# Booster_Capacitor.net
KiCad netlist of a schematic drawn in EAGLE
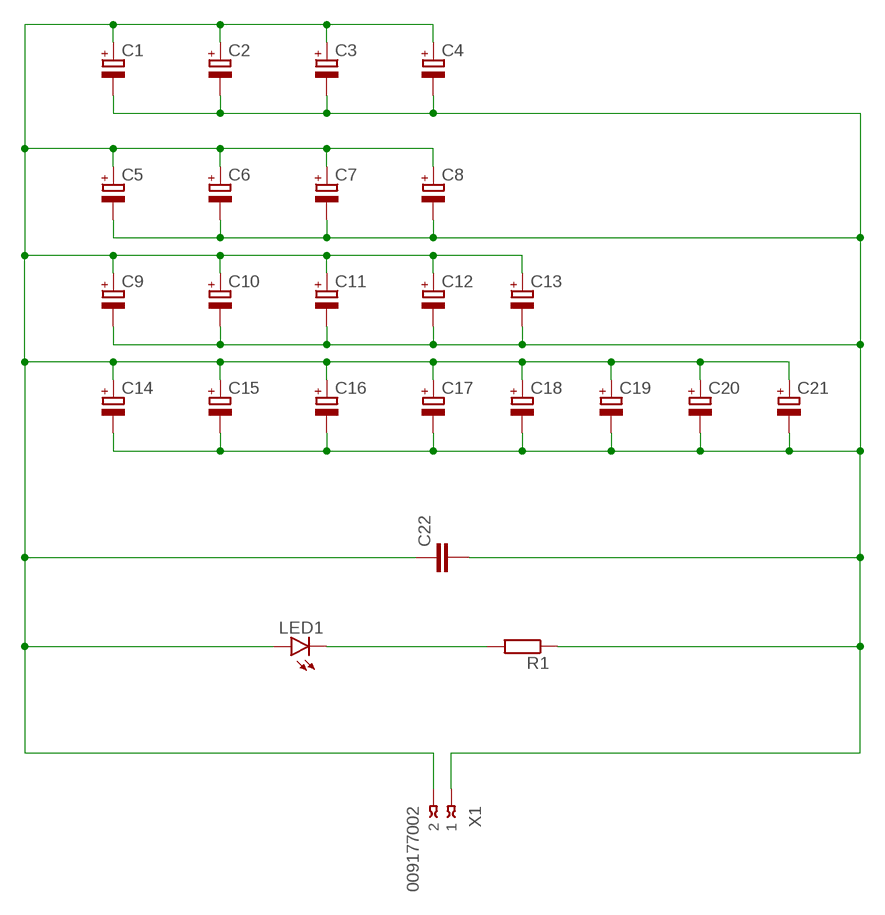
[diagram p0: schematic, sheet 1]

(export (version "E")
  (design (tool "Eeschema 10.0.6"))
  (components
    (comp (ref "C1")
      (value "CPOL-EUE3.5-8")
      (footprint "eagle-import:E3,5-8")
      (libsource (lib "eagle-import") (part "CPOL-EUE3.5-8"))
    )
    (comp (ref "C2")
      (value "CPOL-EUE3.5-8")
      (footprint "eagle-import:E3,5-8")
      (libsource (lib "eagle-import") (part "CPOL-EUE3.5-8"))
    )
    (comp (ref "C3")
      (value "CPOL-EUE3.5-8")
      (footprint "eagle-import:E3,5-8")
      (libsource (lib "eagle-import") (part "CPOL-EUE3.5-8"))
    )
    (comp (ref "C4")
      (value "CPOL-EUE3.5-8")
      (footprint "eagle-import:E3,5-8")
      (libsource (lib "eagle-import") (part "CPOL-EUE3.5-8"))
    )
    (comp (ref "C5")
      (value "CPOL-EUE3.5-8")
      (footprint "eagle-import:E3,5-8")
      (libsource (lib "eagle-import") (part "CPOL-EUE3.5-8"))
    )
    (comp (ref "C6")
      (value "CPOL-EUE3.5-8")
      (footprint "eagle-import:E3,5-8")
      (libsource (lib "eagle-import") (part "CPOL-EUE3.5-8"))
    )
    (comp (ref "C7")
      (value "CPOL-EUE3.5-8")
      (footprint "eagle-import:E3,5-8")
      (libsource (lib "eagle-import") (part "CPOL-EUE3.5-8"))
    )
    (comp (ref "C8")
      (value "CPOL-EUE3.5-8")
      (footprint "eagle-import:E3,5-8")
      (libsource (lib "eagle-import") (part "CPOL-EUE3.5-8"))
    )
    (comp (ref "C9")
      (value "CPOL-EUE2.5-7")
      (footprint "eagle-import:E2,5-7")
      (libsource (lib "eagle-import") (part "CPOL-EUE2.5-7"))
    )
    (comp (ref "C10")
      (value "CPOL-EUE2.5-7")
      (footprint "eagle-import:E2,5-7")
      (libsource (lib "eagle-import") (part "CPOL-EUE2.5-7"))
    )
    (comp (ref "C11")
      (value "CPOL-EUE2.5-7")
      (footprint "eagle-import:E2,5-7")
      (libsource (lib "eagle-import") (part "CPOL-EUE2.5-7"))
    )
    (comp (ref "C12")
      (value "CPOL-EUE2.5-7")
      (footprint "eagle-import:E2,5-7")
      (libsource (lib "eagle-import") (part "CPOL-EUE2.5-7"))
    )
    (comp (ref "C13")
      (value "CPOL-EUE2.5-7")
      (footprint "eagle-import:E2,5-7")
      (libsource (lib "eagle-import") (part "CPOL-EUE2.5-7"))
    )
    (comp (ref "C14")
      (value "CPOL-EUE2.5-6")
      (footprint "eagle-import:E2,5-6")
      (libsource (lib "eagle-import") (part "CPOL-EUE2.5-6"))
    )
    (comp (ref "C15")
      (value "CPOL-EUE2.5-6")
      (footprint "eagle-import:E2,5-6")
      (libsource (lib "eagle-import") (part "CPOL-EUE2.5-6"))
    )
    (comp (ref "C16")
      (value "CPOL-EUE2.5-6")
      (footprint "eagle-import:E2,5-6")
      (libsource (lib "eagle-import") (part "CPOL-EUE2.5-6"))
    )
    (comp (ref "C17")
      (value "CPOL-EUE2.5-6")
      (footprint "eagle-import:E2,5-6")
      (libsource (lib "eagle-import") (part "CPOL-EUE2.5-6"))
    )
    (comp (ref "C18")
      (value "CPOL-EUE2.5-6")
      (footprint "eagle-import:E2,5-6")
      (libsource (lib "eagle-import") (part "CPOL-EUE2.5-6"))
    )
    (comp (ref "C19")
      (value "CPOL-EUE2.5-6")
      (footprint "eagle-import:E2,5-6")
      (libsource (lib "eagle-import") (part "CPOL-EUE2.5-6"))
    )
    (comp (ref "C20")
      (value "CPOL-EUE2.5-6")
      (footprint "eagle-import:E2,5-6")
      (libsource (lib "eagle-import") (part "CPOL-EUE2.5-6"))
    )
    (comp (ref "C21")
      (value "CPOL-EUE2.5-6")
      (footprint "eagle-import:E2,5-6")
      (libsource (lib "eagle-import") (part "CPOL-EUE2.5-6"))
    )
    (comp (ref "C22")
      (value "C-EU025-025X050")
      (footprint "eagle-import:C025-025X050")
      (libsource (lib "eagle-import") (part "C-EU025-025X050"))
    )
    (comp (ref "LED1")
      (value "LED5MM")
      (footprint "eagle-import:LED5MM")
      (libsource (lib "eagle-import") (part "LED5MM"))
    )
    (comp (ref "R1")
      (value "R-EU_0207/10")
      (footprint "eagle-import:0207_10")
      (libsource (lib "eagle-import") (part "R-EU_0207/10"))
    )
    (comp (ref "X1")
      (value "009177002")
      (footprint "eagle-import:009177002")
      (fields (field (name "MPN") "009177002001006"))
      (libsource (lib "eagle-import") (part "00917?0027"))
    )
  )
  (nets
    (net (code "1") (name "Net-(C1-Pad+)") (class "Default")
      (node (ref "C1") (pin "+") (pinfunction "+_+") (pintype "passive"))
      (node (ref "C10") (pin "+") (pinfunction "+_+") (pintype "passive"))
      (node (ref "C11") (pin "+") (pinfunction "+_+") (pintype "passive"))
      (node (ref "C12") (pin "+") (pinfunction "+_+") (pintype "passive"))
      (node (ref "C13") (pin "+") (pinfunction "+_+") (pintype "passive"))
      (node (ref "C14") (pin "+") (pinfunction "+_+") (pintype "passive"))
      (node (ref "C15") (pin "+") (pinfunction "+_+") (pintype "passive"))
      (node (ref "C16") (pin "+") (pinfunction "+_+") (pintype "passive"))
      (node (ref "C17") (pin "+") (pinfunction "+_+") (pintype "passive"))
      (node (ref "C18") (pin "+") (pinfunction "+_+") (pintype "passive"))
      (node (ref "C19") (pin "+") (pinfunction "+_+") (pintype "passive"))
      (node (ref "C2") (pin "+") (pinfunction "+_+") (pintype "passive"))
      (node (ref "C20") (pin "+") (pinfunction "+_+") (pintype "passive"))
      (node (ref "C21") (pin "+") (pinfunction "+_+") (pintype "passive"))
      (node (ref "C22") (pin "1") (pinfunction "1_1") (pintype "passive"))
      (node (ref "C3") (pin "+") (pinfunction "+_+") (pintype "passive"))
      (node (ref "C4") (pin "+") (pinfunction "+_+") (pintype "passive"))
      (node (ref "C5") (pin "+") (pinfunction "+_+") (pintype "passive"))
      (node (ref "C6") (pin "+") (pinfunction "+_+") (pintype "passive"))
      (node (ref "C7") (pin "+") (pinfunction "+_+") (pintype "passive"))
      (node (ref "C8") (pin "+") (pinfunction "+_+") (pintype "passive"))
      (node (ref "C9") (pin "+") (pinfunction "+_+") (pintype "passive"))
      (node (ref "LED1") (pin "A") (pinfunction "A_A") (pintype "passive"))
      (node (ref "X1") (pin "2") (pinfunction "2_2") (pintype "passive"))
    )
    (net (code "2") (name "Net-(C1-Pad-)") (class "Default")
      (node (ref "C1") (pin "-") (pinfunction "-_-") (pintype "passive"))
      (node (ref "C10") (pin "-") (pinfunction "-_-") (pintype "passive"))
      (node (ref "C11") (pin "-") (pinfunction "-_-") (pintype "passive"))
      (node (ref "C12") (pin "-") (pinfunction "-_-") (pintype "passive"))
      (node (ref "C13") (pin "-") (pinfunction "-_-") (pintype "passive"))
      (node (ref "C14") (pin "-") (pinfunction "-_-") (pintype "passive"))
      (node (ref "C15") (pin "-") (pinfunction "-_-") (pintype "passive"))
      (node (ref "C16") (pin "-") (pinfunction "-_-") (pintype "passive"))
      (node (ref "C17") (pin "-") (pinfunction "-_-") (pintype "passive"))
      (node (ref "C18") (pin "-") (pinfunction "-_-") (pintype "passive"))
      (node (ref "C19") (pin "-") (pinfunction "-_-") (pintype "passive"))
      (node (ref "C2") (pin "-") (pinfunction "-_-") (pintype "passive"))
      (node (ref "C20") (pin "-") (pinfunction "-_-") (pintype "passive"))
      (node (ref "C21") (pin "-") (pinfunction "-_-") (pintype "passive"))
      (node (ref "C22") (pin "2") (pinfunction "2_2") (pintype "passive"))
      (node (ref "C3") (pin "-") (pinfunction "-_-") (pintype "passive"))
      (node (ref "C4") (pin "-") (pinfunction "-_-") (pintype "passive"))
      (node (ref "C5") (pin "-") (pinfunction "-_-") (pintype "passive"))
      (node (ref "C6") (pin "-") (pinfunction "-_-") (pintype "passive"))
      (node (ref "C7") (pin "-") (pinfunction "-_-") (pintype "passive"))
      (node (ref "C8") (pin "-") (pinfunction "-_-") (pintype "passive"))
      (node (ref "C9") (pin "-") (pinfunction "-_-") (pintype "passive"))
      (node (ref "R1") (pin "1") (pinfunction "1_1") (pintype "passive"))
      (node (ref "X1") (pin "1") (pinfunction "1_1") (pintype "passive"))
    )
    (net (code "3") (name "Net-(LED1-C)") (class "Default")
      (node (ref "LED1") (pin "K") (pinfunction "C_K") (pintype "passive"))
      (node (ref "R1") (pin "2") (pinfunction "2_2") (pintype "passive"))
    )
  )
)
